# ALARM.net
KiCad netlist of a schematic drawn in Altium Designer
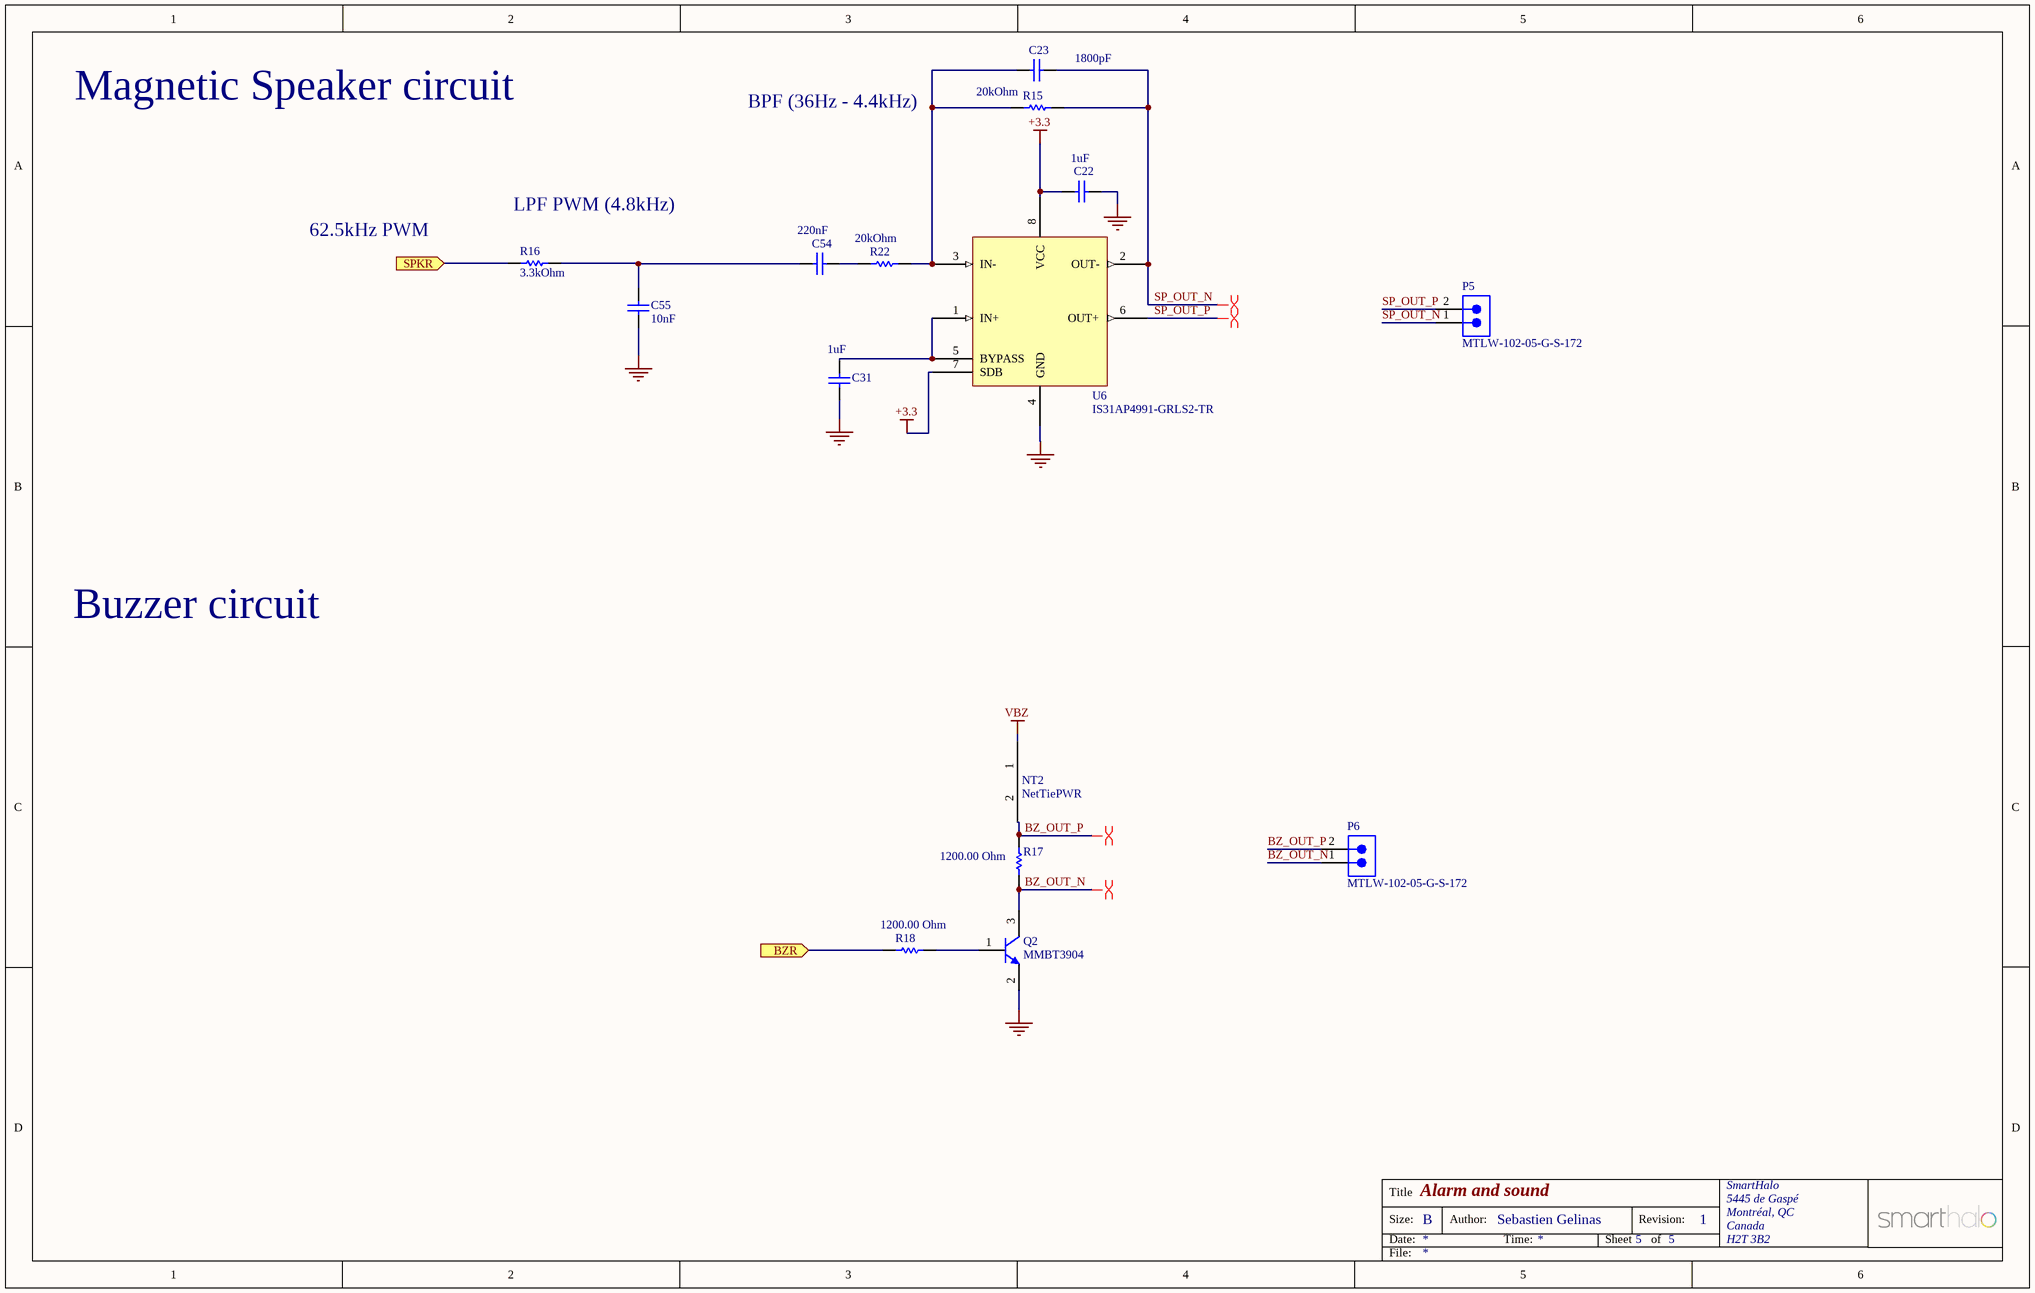
[diagram p0: ALARM.SchDoc]

(export (version "E")
  (design (tool "Eeschema 10.0.6"))
  (components
    (comp (ref "C22")
      (value "CAP 1uF 6.3V 0402(1005)")
      (footprint "CAPC0402(1005)60_L")
      (description "CAP 1uF 6.3V ±10% 0402 (1005 Metric)")
      (fields (field (name "CAPACITANCE") "1uF") (field (name "TOLERANCE") "±10%"))
      (libsource (lib "Altium Content Vault") (part "CMP-1034-02113-1"))
    )
    (comp (ref "C23")
      (value "CAP 1800pF 6.3V 0402(1005)")
      (footprint "CAPC0402(1005)60_N")
      (description "CAP 1800pF 6.3V ±10% 0402 (1005 Metric)")
      (fields (field (name "CAPACITANCE") "1800pF") (field (name "TOLERANCE") "±10%"))
      (libsource (lib "Altium Content Vault") (part "CMP-1034-01350-1"))
    )
    (comp (ref "C31")
      (value "CAP 1uF 6.3V 0402(1005)")
      (footprint "CAPC0402(1005)60_L")
      (description "CAP 1uF 6.3V ±10% 0402 (1005 Metric)")
      (fields (field (name "CAPACITANCE") "1uF") (field (name "TOLERANCE") "±10%"))
      (libsource (lib "Altium Content Vault") (part "CMP-1034-02113-1"))
    )
    (comp (ref "C54")
      (value "CAP 220nF 6.3V 0402(1005)")
      (footprint "CAPC0402(1005)60_N")
      (description "CAP 220nF 6.3V ±10% 0402 (1005 Metric)")
      (fields (field (name "CAPACITANCE") "220nF") (field (name "TOLERANCE") "±10%"))
      (libsource (lib "Altium Content Vault") (part "CMP-1034-01350-1"))
    )
    (comp (ref "C55")
      (value "CAP 10nF 6.3V 0402(1005)")
      (footprint "CAPC0402(1005)60_N")
      (description "CAP 10nF 6.3V ±10% 0402 (1005 Metric)")
      (fields (field (name "CAPACITANCE") "10nF") (field (name "TOLERANCE") "±10%"))
      (libsource (lib "Altium Content Vault") (part "CMP-1034-01350-1"))
    )
    (comp (ref "NT2")
      (value "NetTiePWR")
      (footprint "NetTiePWR")
      (libsource (lib "Schlib1") (part "NetTiePWR"))
    )
    (comp (ref "P5")
      (value "MTLW-102-05-G-S-172")
      (footprint "SMTC-MTLW-102-05-X-S-172")
      (fields (field (name "MANUFACTURER") "Samtec"))
      (libsource (lib "Altium Content Vault") (part "CMP-1024-00064-1"))
    )
    (comp (ref "P6")
      (value "MTLW-102-05-G-S-172")
      (footprint "SMTC-MTLW-102-05-X-S-172")
      (fields (field (name "MANUFACTURER") "Samtec"))
      (libsource (lib "Altium Content Vault") (part "CMP-1024-00064-1"))
    )
    (comp (ref "Q2")
      (value "MMBT3904")
      (footprint "INF-SOT23_L")
      (description "NPN Silicon Switching Transistor, 40 V VCEO, 200 mA IC, SOT23, Reel, Green")
      (fields (field (name "MANUFACTURER") "Infineon"))
      (libsource (lib "Altium Content Vault") (part "INF-BJTNPN-BEC-3"))
    )
    (comp (ref "R15")
      (value "20K 5% 0402(1005)")
      (footprint "RESC0402(1005)_M")
      (description "20K 0.063W ±5% 0402 (1005 Metric)")
      (fields
        (field (name "TOLERANCE") "±5 %")
        (field (name "RESISTANCE") "20kOhm")
        (field (name "POWER") "0.063 W")
      )
      (libsource (lib "Altium Content Vault") (part "CMP-1011-00105-1"))
    )
    (comp (ref "R16")
      (value "3K3 5% 0402(1005)")
      (footprint "RESC0402(1005)_M")
      (description "3K3 0.063W ±5% 0402 (1005 Metric)  SMD")
      (fields
        (field (name "TOLERANCE") "±5 %")
        (field (name "RESISTANCE") "3.3kOhm")
        (field (name "POWER") "0.063 W")
      )
      (libsource (lib "Altium Content Vault") (part "CMP-1011-00105-1"))
    )
    (comp (ref "R17")
      (value "1K2 ±5% 0402(1005)")
      (footprint "RESC0402(1005)_N")
      (description "1K2 0.063W ±5% 0402 (1005 Metric)")
      (fields
        (field (name "RESISTANCE") "1200.00 Ohm")
        (field (name "POWER") "0.063 W")
        (field (name "TOLERANCE") "±5 %")
      )
      (libsource (lib "Altium Content Vault") (part "CMP-1011-00076-1"))
    )
    (comp (ref "R18")
      (value "1K2 5% 0402(1005)")
      (footprint "RESC0402(1005)_N")
      (description "1K2 0.063W ±5% 0402 (1005 Metric)  SMD")
      (fields
        (field (name "RESISTANCE") "1200.00 Ohm")
        (field (name "POWER") "0.063 W")
        (field (name "TOLERANCE") "±5 %")
      )
      (libsource (lib "Altium Content Vault") (part "CMP-1011-00076-1"))
    )
    (comp (ref "R22")
      (value "20K 5% 0402(1005)")
      (footprint "RESC0402(1005)_M")
      (description "20K 0.063W ±5% 0402 (1005 Metric)")
      (fields
        (field (name "TOLERANCE") "±5 %")
        (field (name "RESISTANCE") "20kOhm")
        (field (name "POWER") "0.063 W")
      )
      (libsource (lib "Altium Content Vault") (part "CMP-1011-00105-1"))
    )
    (comp (ref "U6")
      (value "IS31AP4991-GRLS2-TR")
      (footprint "SmartHalo:SOP8")
      (description "IC AUDIO AMP MONO 1.2W 8SOP")
      (libsource (lib "SmartHalo") (part "IS31AP4991-GRLS2-TR"))
    )
  )
  (nets
    (net (code "1") (name "+3.3") (class "Default")
      (node (ref "C22") (pin "2") (pinfunction "2_2") (pintype "passive"))
      (node (ref "U6") (pin "7") (pinfunction "SDB_7") (pintype "passive"))
      (node (ref "U6") (pin "8") (pinfunction "VCC_8") (pintype "power_in"))
    )
    (net (code "2") (name "/BZR") (class "Default")
      (node (ref "R18") (pin "1") (pinfunction "1_1") (pintype "passive"))
    )
    (net (code "3") (name "/BZ_OUT_N") (class "Default")
      (node (ref "P6") (pin "1") (pinfunction "1_1") (pintype "passive"))
      (node (ref "Q2") (pin "3") (pinfunction "C_3") (pintype "passive"))
      (node (ref "R17") (pin "1") (pinfunction "1_1") (pintype "passive"))
    )
    (net (code "4") (name "/BZ_OUT_P") (class "Default")
      (node (ref "NT2") (pin "2") (pinfunction "NET2_2") (pintype "passive"))
      (node (ref "P6") (pin "2") (pinfunction "2_2") (pintype "passive"))
      (node (ref "R17") (pin "2") (pinfunction "2_2") (pintype "passive"))
    )
    (net (code "5") (name "/SPKR") (class "Default")
      (node (ref "R16") (pin "2") (pinfunction "2_2") (pintype "passive"))
    )
    (net (code "6") (name "/SP_OUT_N") (class "Default")
      (node (ref "C23") (pin "2") (pinfunction "2_2") (pintype "passive"))
      (node (ref "P5") (pin "1") (pinfunction "1_1") (pintype "passive"))
      (node (ref "R15") (pin "2") (pinfunction "2_2") (pintype "passive"))
      (node (ref "U6") (pin "2") (pinfunction "OUT-_2") (pintype "output"))
    )
    (net (code "7") (name "/SP_OUT_P") (class "Default")
      (node (ref "P5") (pin "2") (pinfunction "2_2") (pintype "passive"))
      (node (ref "U6") (pin "6") (pinfunction "OUT+_6") (pintype "output"))
    )
    (net (code "8") (name "GND") (class "Default")
      (node (ref "C22") (pin "1") (pinfunction "1_1") (pintype "passive"))
      (node (ref "C31") (pin "1") (pinfunction "1_1") (pintype "passive"))
      (node (ref "C55") (pin "1") (pinfunction "1_1") (pintype "passive"))
      (node (ref "Q2") (pin "2") (pinfunction "E_2") (pintype "passive"))
      (node (ref "U6") (pin "4") (pinfunction "GND_4") (pintype "power_in"))
    )
    (net (code "9") (name "Net-(C54-Pad1)") (class "Default")
      (node (ref "C54") (pin "1") (pinfunction "1_1") (pintype "passive"))
      (node (ref "C55") (pin "2") (pinfunction "2_2") (pintype "passive"))
      (node (ref "R16") (pin "1") (pinfunction "1_1") (pintype "passive"))
    )
    (net (code "10") (name "Net-(C54-Pad2)") (class "Default")
      (node (ref "C54") (pin "2") (pinfunction "2_2") (pintype "passive"))
      (node (ref "R22") (pin "1") (pinfunction "1_1") (pintype "passive"))
    )
    (net (code "11") (name "Net-(Q2-B)") (class "Default")
      (node (ref "Q2") (pin "1") (pinfunction "B_1") (pintype "passive"))
      (node (ref "R18") (pin "2") (pinfunction "2_2") (pintype "passive"))
    )
    (net (code "12") (name "Net-(U6-BYPASS)") (class "Default")
      (node (ref "C31") (pin "2") (pinfunction "2_2") (pintype "passive"))
      (node (ref "U6") (pin "1") (pinfunction "IN+_1") (pintype "input"))
      (node (ref "U6") (pin "5") (pinfunction "BYPASS_5") (pintype "passive"))
    )
    (net (code "13") (name "Net-(U6-IN-)") (class "Default")
      (node (ref "C23") (pin "1") (pinfunction "1_1") (pintype "passive"))
      (node (ref "R15") (pin "1") (pinfunction "1_1") (pintype "passive"))
      (node (ref "R22") (pin "2") (pinfunction "2_2") (pintype "passive"))
      (node (ref "U6") (pin "3") (pinfunction "IN-_3") (pintype "input"))
    )
    (net (code "14") (name "VBZ") (class "Default")
      (node (ref "NT2") (pin "1") (pinfunction "NET1_1") (pintype "passive"))
    )
  )
)
